# schematic.net
KiCad netlist of a schematic drawn in EasyEDA
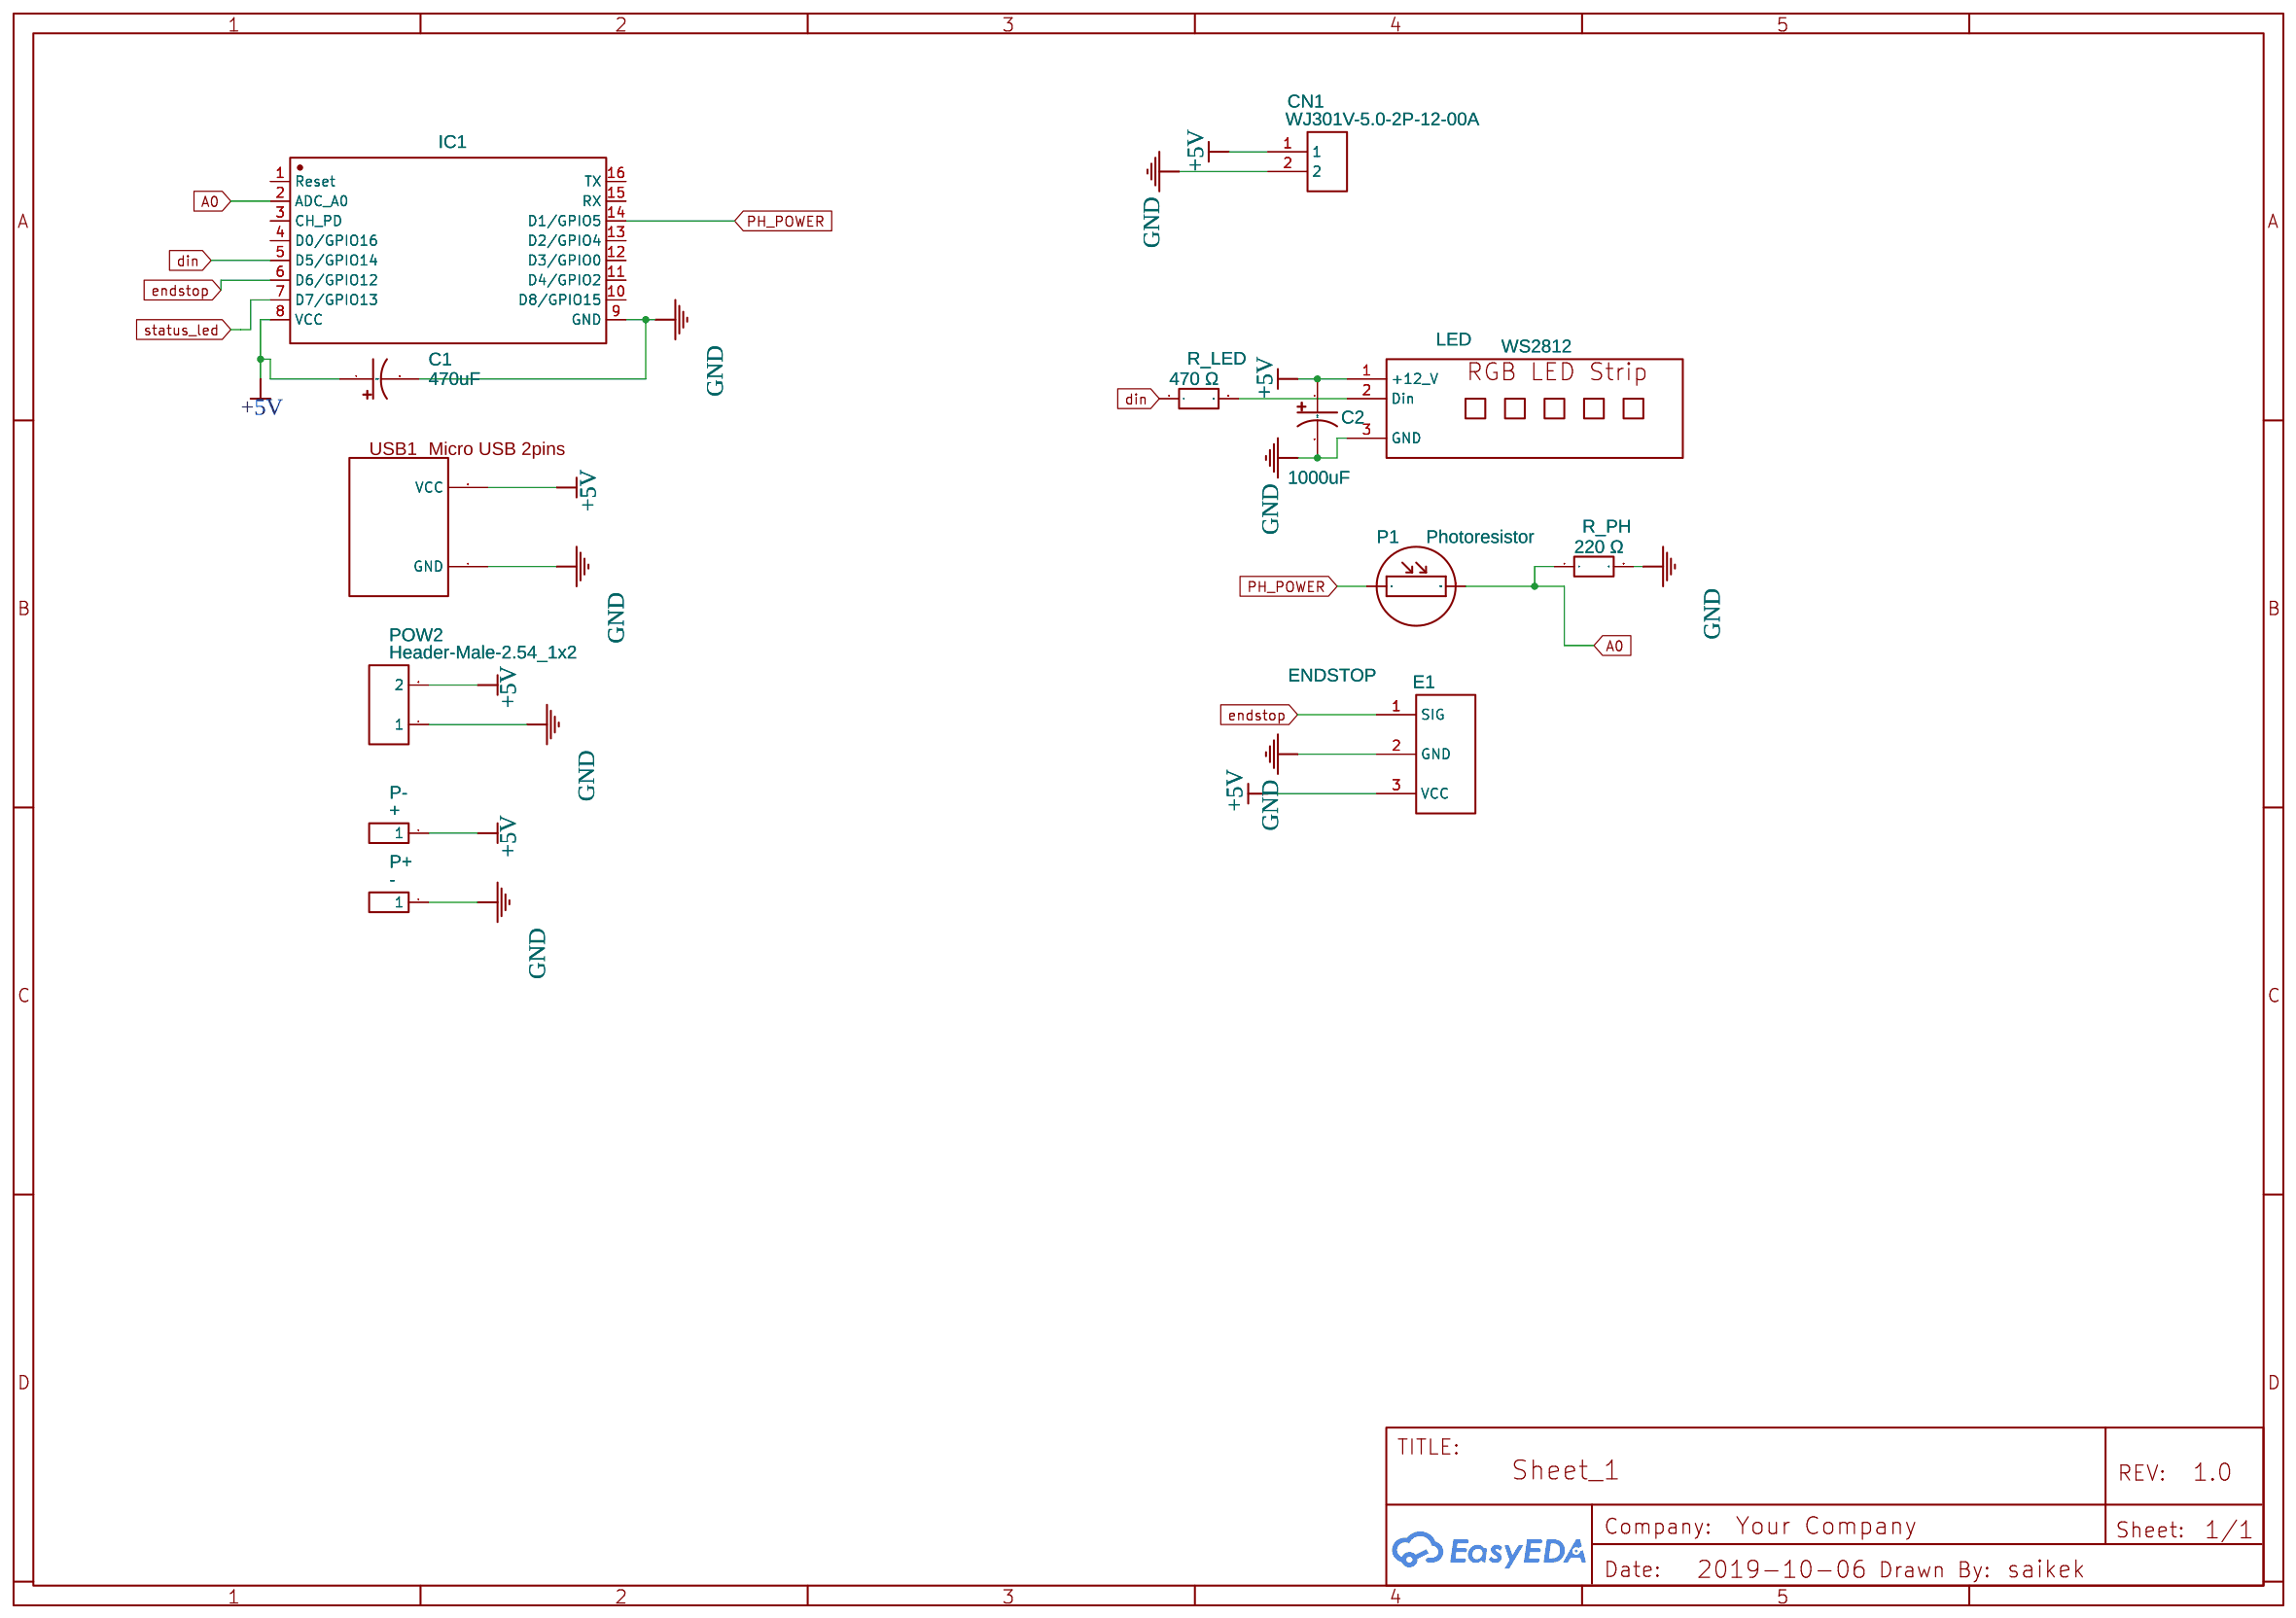
[diagram p0: schematic sheet]

(export (version "E")
  (design (tool "Eeschema 10.0.6"))
  (components
    (comp (ref "C1")
      (value "470uF")
      (fields
        (field (name "BOM_Manufacturer Part") "VE-471M0JTR-0607")
        (field (name "BOM_Supplier Part") "C134738")
      )
      (libsource (lib "") (part "VE-471M0JTR-0607"))
    )
    (comp (ref "C2")
      (value "1000uF")
      (fields
        (field (name "BOM_Manufacturer Part") "RT0J102M0810")
        (field (name "BOM_Supplier Part") "C280405")
      )
      (libsource (lib "") (part "RT0J102M0810"))
    )
    (comp (ref "CN1")
      (value "WJ301V-5.0-2P-12-00A")
      (fields (field (name "BOM_Supplier Part") "undefined"))
      (libsource (lib "") (part "Unknown_655_75"))
    )
    (comp (ref "ENDSTOP")
      (value "E1")
      (fields (field (name "BOM_Manufacturer Part") "New SchematicLib"))
      (libsource (lib "") (part "Unknown_690_355"))
    )
    (comp (ref "IC1") (value "Witty") (libsource (lib "") (part "Unknown_220_75")))
    (comp (ref "LED") (value "WS2812") (libsource (lib "") (part "RGB_LED_Strip_WS2812B")))
    (comp (ref "P+")
      (value "-")
      (fields
        (field (name "BOM_Manufacturer Part") "Header-Male-2.54_1x1")
        (field (name "BOM_Supplier Part") "C81276")
      )
      (libsource (lib "") (part "Unknown_195_450"))
    )
    (comp (ref "P-")
      (value "+")
      (fields
        (field (name "BOM_Manufacturer Part") "Header-Male-2.54_1x1")
        (field (name "BOM_Supplier Part") "C81276")
      )
      (libsource (lib "") (part "Unknown_195_415"))
    )
    (comp (ref "P1")
      (value "Photoresistor")
      (fields (field (name "BOM_Manufacturer Part") "Photoresistor-5528"))
      (libsource (lib "") (part "Unknown_710_290"))
    )
    (comp (ref "POW2")
      (value "Header-Male-2.54_1x2")
      (fields (field (name "BOM_Manufacturer Part") "826629-2") (field (name "BOM_Supplier Part") "C86471"))
      (libsource (lib "") (part "Unknown_195_350"))
    )
    (comp (ref "R_LED") (value "470 Ω") (libsource (lib "") (part "Res_1206(1/4W)_EU_1")))
    (comp (ref "R_PH") (value "220 Ω") (libsource (lib "") (part "Res_1206(1/4W)_EU")))
    (comp (ref "U2") (value "MicroUSB 2 pins female") (libsource (lib "") (part "Unknown_200_260")))
  )
  (nets
    (net (code "1") (name "+5V") (class "Default")
      (node (ref "C1") (pin "1") (pinfunction "1_1") (pintype "unspecified"))
      (node (ref "C2") (pin "1") (pinfunction "1_1") (pintype "unspecified"))
      (node (ref "CN1") (pin "1") (pinfunction "1_1") (pintype "unspecified"))
      (node (ref "ENDSTOP") (pin "3") (pinfunction "VCC_3") (pintype "unspecified"))
      (node (ref "IC1") (pin "8") (pinfunction "VCC_8") (pintype "unspecified"))
      (node (ref "LED") (pin "1") (pinfunction "+12_V_1") (pintype "unspecified"))
      (node (ref "P-") (pin "1") (pinfunction "1_1") (pintype "input"))
      (node (ref "POW2") (pin "2") (pinfunction "2_2") (pintype "unspecified"))
      (node (ref "U2") (pin "2") (pinfunction "VCC_2") (pintype "unspecified"))
    )
    (net (code "2") (name "A0") (class "Default")
      (node (ref "IC1") (pin "2") (pinfunction "ADC_A0_2") (pintype "unspecified"))
      (node (ref "P1") (pin "2") (pinfunction "P$2_2") (pintype "unspecified"))
      (node (ref "R_PH") (pin "1") (pinfunction "1_1") (pintype "unspecified"))
    )
    (net (code "3") (name "GND") (class "Default")
      (node (ref "C1") (pin "2") (pinfunction "2_2") (pintype "unspecified"))
      (node (ref "C2") (pin "2") (pinfunction "2_2") (pintype "unspecified"))
      (node (ref "CN1") (pin "2") (pinfunction "2_2") (pintype "unspecified"))
      (node (ref "ENDSTOP") (pin "2") (pinfunction "GND_2") (pintype "unspecified"))
      (node (ref "IC1") (pin "9") (pinfunction "GND_9") (pintype "unspecified"))
      (node (ref "LED") (pin "3") (pinfunction "GND_3") (pintype "unspecified"))
      (node (ref "P+") (pin "1") (pinfunction "1_1") (pintype "input"))
      (node (ref "POW2") (pin "1") (pinfunction "1_1") (pintype "unspecified"))
      (node (ref "R_PH") (pin "2") (pinfunction "2_2") (pintype "unspecified"))
      (node (ref "U2") (pin "1") (pinfunction "GND_1") (pintype "unspecified"))
    )
    (net (code "4") (name "Net-(LED-Din)") (class "Default")
      (node (ref "LED") (pin "2") (pinfunction "Din_2") (pintype "input"))
      (node (ref "R_LED") (pin "2") (pinfunction "2_2") (pintype "unspecified"))
    )
    (net (code "5") (name "PH_POWER") (class "Default")
      (node (ref "IC1") (pin "14") (pinfunction "D1/GPIO5_14") (pintype "unspecified"))
      (node (ref "P1") (pin "1") (pinfunction "P$1_1") (pintype "unspecified"))
    )
    (net (code "6") (name "din") (class "Default")
      (node (ref "IC1") (pin "5") (pinfunction "D5/GPIO14_5") (pintype "unspecified"))
      (node (ref "R_LED") (pin "1") (pinfunction "1_1") (pintype "unspecified"))
    )
    (net (code "7") (name "endstop") (class "Default")
      (node (ref "ENDSTOP") (pin "1") (pinfunction "SIG_1") (pintype "unspecified"))
      (node (ref "IC1") (pin "6") (pinfunction "D6/GPIO12_6") (pintype "unspecified"))
    )
    (net (code "8") (name "status_led") (class "Default")
      (node (ref "IC1") (pin "7") (pinfunction "D7/GPIO13_7") (pintype "unspecified"))
    )
    (net (code "9") (name "unconnected-(IC1-CH_PD-Pad3)") (class "Default")
      (node (ref "IC1") (pin "3") (pinfunction "CH_PD_3") (pintype "unspecified"))
    )
    (net (code "10") (name "unconnected-(IC1-D0{slash}GPIO16-Pad4)") (class "Default")
      (node (ref "IC1") (pin "4") (pinfunction "D0/GPIO16_4") (pintype "unspecified"))
    )
    (net (code "11") (name "unconnected-(IC1-D2{slash}GPIO4-Pad13)") (class "Default")
      (node (ref "IC1") (pin "13") (pinfunction "D2/GPIO4_13") (pintype "unspecified"))
    )
    (net (code "12") (name "unconnected-(IC1-D3{slash}GPIO0-Pad12)") (class "Default")
      (node (ref "IC1") (pin "12") (pinfunction "D3/GPIO0_12") (pintype "unspecified"))
    )
    (net (code "13") (name "unconnected-(IC1-D4{slash}GPIO2-Pad11)") (class "Default")
      (node (ref "IC1") (pin "11") (pinfunction "D4/GPIO2_11") (pintype "unspecified"))
    )
    (net (code "14") (name "unconnected-(IC1-D8{slash}GPIO15-Pad10)") (class "Default")
      (node (ref "IC1") (pin "10") (pinfunction "D8/GPIO15_10") (pintype "unspecified"))
    )
    (net (code "15") (name "unconnected-(IC1-RX-Pad15)") (class "Default")
      (node (ref "IC1") (pin "15") (pinfunction "RX_15") (pintype "unspecified"))
    )
    (net (code "16") (name "unconnected-(IC1-Reset-Pad1)") (class "Default")
      (node (ref "IC1") (pin "1") (pinfunction "Reset_1") (pintype "unspecified"))
    )
    (net (code "17") (name "unconnected-(IC1-TX-Pad16)") (class "Default")
      (node (ref "IC1") (pin "16") (pinfunction "TX_16") (pintype "unspecified"))
    )
  )
)
